# CANbus.net
KiCad netlist of a schematic drawn in Altium Designer
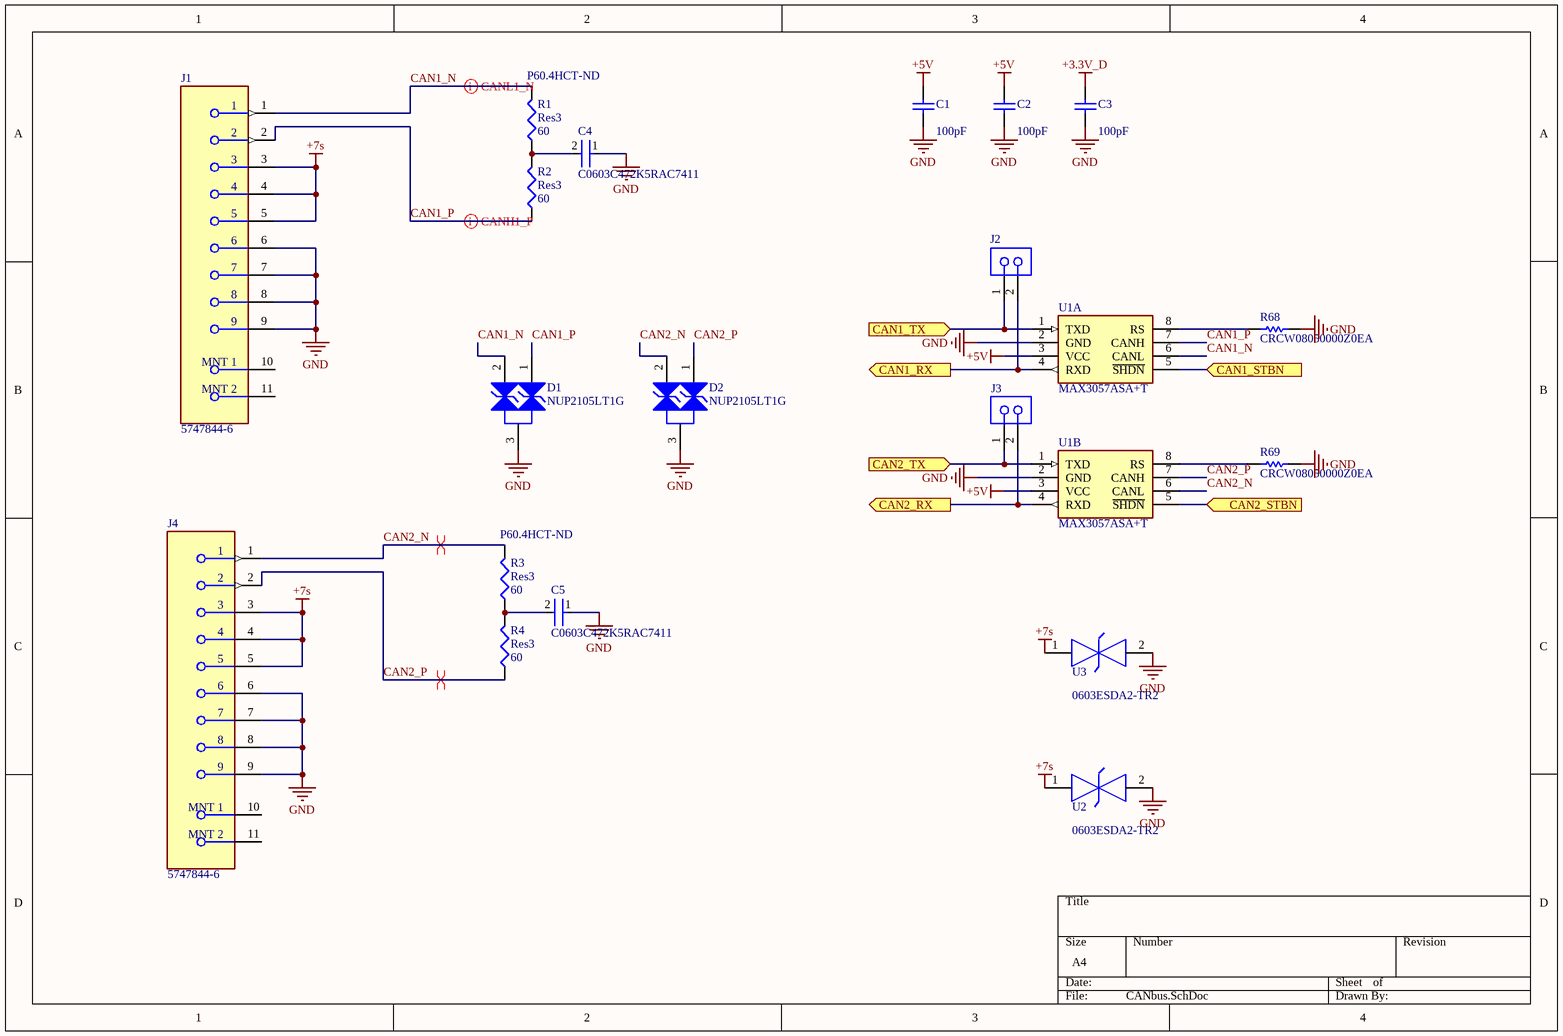
[diagram p0: CANbus.SchDoc]

(export (version "E")
  (design (tool "Eeschema 10.0.6"))
  (components
    (comp (ref "C1")
      (value "100pF")
      (footprint "CAPC1608X90X35NL10T15")
      (fields (field (name "PART NUMBER") "GRM1885C1H101JA01D") (field (name "MANUFACTURER") "Murata"))
      (libsource (lib "Altium Content Vault") (part "CAP"))
    )
    (comp (ref "C2")
      (value "100pF")
      (footprint "CAPC1608X90X35NL10T15")
      (fields (field (name "PART NUMBER") "GRM1885C1H101JA01D") (field (name "MANUFACTURER") "Murata"))
      (libsource (lib "Altium Content Vault") (part "CAP"))
    )
    (comp (ref "C3")
      (value "100pF")
      (footprint "CAPC1608X90X35NL10T15")
      (fields (field (name "PART NUMBER") "GRM1885C1H101JA01D") (field (name "MANUFACTURER") "Murata"))
      (libsource (lib "Altium Content Vault") (part "CAP"))
    )
    (comp (ref "C4")
      (value "C0603C472K5RAC7411")
      (footprint "FP-C0603C-CF-MFG")
      (description "C0603 4,700 pF X7R 30ppm/°C 10.00% 50 V")
      (fields
        (field (name "OCTOPART") "https://octopart.com/c0603c472k5rac7411-kemet-3746251")
        (field (name "TOLERANCE") "0.1")
      )
      (libsource (lib "Altium Content Vault") (part "b4654b650e69147ec39a6b967a45e02"))
    )
    (comp (ref "C5")
      (value "C0603C472K5RAC7411")
      (footprint "FP-C0603C-CF-MFG")
      (description "C0603 4,700 pF X7R 30ppm/°C 10.00% 50 V")
      (fields
        (field (name "OCTOPART") "https://octopart.com/c0603c472k5rac7411-kemet-3746251")
        (field (name "TOLERANCE") "0.1")
      )
      (libsource (lib "Altium Content Vault") (part "b4654b650e69147ec39a6b967a45e02"))
    )
    (comp (ref "D1")
      (value "NUP2105LT1G")
      (footprint "ONSC-SOT-23-3-318-08_V")
      (description "Dual Line CAN Bus Protector, 3-Pin SOT-23, Pb-Free, Tape and Reel")
      (fields (field (name "MANUFACTURER") "On Semiconductor"))
      (libsource (lib "Altium Content Vault") (part "ONSC-NUP21X5X-SOT-23-3-318-08"))
    )
    (comp (ref "D2")
      (value "NUP2105LT1G")
      (footprint "ONSC-SOT-23-3-318-08_V")
      (description "Dual Line CAN Bus Protector, 3-Pin SOT-23, Pb-Free, Tape and Reel")
      (fields (field (name "MANUFACTURER") "On Semiconductor"))
      (libsource (lib "Altium Content Vault") (part "ONSC-NUP21X5X-SOT-23-3-318-08"))
    )
    (comp (ref "J1")
      (value "5747844-6")
      (footprint "FP-5747844-6-MFG")
      (description "CONN D-SUB RCPT 9POS R/A SOLDER")
      (fields
        (field (name "MANUFACTURER") "TE Connectivity")
        (field (name "OCTOPART") "https://octopart.com/5747844-6-te+connectivity-46505427")
      )
      (libsource (lib "Altium Content Vault") (part "18082bb167a0522e34c03a238bc0119"))
    )
    (comp (ref "J2")
      (value "SSW-102-02-T-S")
      (footprint "SMTC-SSW-102-02-X-S")
      (description "SQ Post Socket, Through-hole, Vertical, -55 to 105 degC, 2.54 mm Pitch, 2-Pin, Female, RoHS")
      (fields (field (name "MANUFACTURER") "Samtec"))
      (libsource (lib "Altium Content Vault") (part "SMTC-SSW-102-02-X-S-X"))
    )
    (comp (ref "J3")
      (value "SSW-102-02-T-S")
      (footprint "SMTC-SSW-102-02-X-S")
      (description "SQ Post Socket, Through-hole, Vertical, -55 to 105 degC, 2.54 mm Pitch, 2-Pin, Female, RoHS")
      (fields (field (name "MANUFACTURER") "Samtec"))
      (libsource (lib "Altium Content Vault") (part "SMTC-SSW-102-02-X-S-X"))
    )
    (comp (ref "J4")
      (value "5747844-6")
      (footprint "FP-5747844-6-MFG")
      (description "CONN D-SUB RCPT 9POS R/A SOLDER")
      (fields
        (field (name "MANUFACTURER") "TE Connectivity")
        (field (name "OCTOPART") "https://octopart.com/5747844-6-te+connectivity-46505427")
      )
      (libsource (lib "Altium Content Vault") (part "18082bb167a0522e34c03a238bc0119"))
    )
    (comp (ref "R1")
      (value "Res3")
      (footprint "J1-0603")
      (description "RESISTOR, 0603, 60R4 1%, 0.1W")
      (fields
        (field (name "ALTIUM_VALUE") "60")
        (field (name "SUPPLIER PART NUMBER 1") "P60.4HCT-ND")
        (field (name "MANUFACTURER") "Panasonic")
        (field (name "MANUFACTURER PART NUMBER") "ERJ-3EKF60R4V")
        (field (name "PUBLISHER") "Altium Limited")
      )
      (libsource (lib "Miscellaneous Devices") (part "Res3"))
    )
    (comp (ref "R2")
      (value "Res3")
      (footprint "J1-0603")
      (description "RESISTOR, 0603, 60R4 1%, 0.1W")
      (fields
        (field (name "ALTIUM_VALUE") "60")
        (field (name "MANUFACTURER") "Panasonic")
        (field (name "MANUFACTURER PART NUMBER") "ERJ-3EKF60R4V")
        (field (name "PUBLISHER") "Altium Limited")
      )
      (libsource (lib "Miscellaneous Devices") (part "Res3"))
    )
    (comp (ref "R3")
      (value "Res3")
      (footprint "J1-0603")
      (description "RESISTOR, 0603, 60R4 1%, 0.1W")
      (fields
        (field (name "ALTIUM_VALUE") "60")
        (field (name "SUPPLIER PART NUMBER 1") "P60.4HCT-ND")
        (field (name "MANUFACTURER") "Panasonic")
        (field (name "MANUFACTURER PART NUMBER") "ERJ-3EKF60R4V")
        (field (name "PUBLISHER") "Altium Limited")
      )
      (libsource (lib "Miscellaneous Devices") (part "Res3"))
    )
    (comp (ref "R4")
      (value "Res3")
      (footprint "J1-0603")
      (description "RESISTOR, 0603, 60R4 1%, 0.1W")
      (fields
        (field (name "ALTIUM_VALUE") "60")
        (field (name "MANUFACTURER") "Panasonic")
        (field (name "MANUFACTURER PART NUMBER") "ERJ-3EKF60R4V")
        (field (name "PUBLISHER") "Altium Limited")
      )
      (libsource (lib "Miscellaneous Devices") (part "Res3"))
    )
    (comp (ref "R68")
      (value "CRCW08050000Z0EA")
      (footprint "RESC2013X50X30LL20T20")
      (fields (field (name "MANUFACTURER") "Vishay Dale"))
      (libsource (lib "Altium Content Vault") (part "RES"))
    )
    (comp (ref "R69")
      (value "CRCW08050000Z0EA")
      (footprint "RESC2013X50X30LL20T20")
      (fields (field (name "MANUFACTURER") "Vishay Dale"))
      (libsource (lib "Altium Content Vault") (part "RES"))
    )
    (comp (ref "U1A")
      (value "MAX3057ASA+T")
      (footprint "SamacSys:SOIC127P600X175-8N")
      (description "Integrated Circuit")
      (libsource (lib "*") (part "MAX3057ASA+T"))
    )
    (comp (ref "U1B")
      (value "MAX3057ASA+T")
      (footprint "SamacSys:SOIC127P600X175-8N")
      (description "Integrated Circuit")
      (libsource (lib "*") (part "MAX3057ASA+T"))
    )
    (comp (ref "U2")
      (value "0603ESDA2-TR2")
      (footprint "Eaton_0603ESDA_0")
      (description "DIODE SUPPRESSOR ESD 30VDC 0603 SMD")
      (fields (field (name "DIGIKEY PART NUMBER") "283-4156-1-ND") (field (name "MANUFACTURER") "Eaton"))
      (libsource (lib "EEConcierge") (part "0603ESDA2-TR2"))
    )
    (comp (ref "U3")
      (value "0603ESDA2-TR2")
      (footprint "Eaton_0603ESDA_0")
      (description "DIODE SUPPRESSOR ESD 30VDC 0603 SMD")
      (fields (field (name "DIGIKEY PART NUMBER") "283-4156-1-ND") (field (name "MANUFACTURER") "Eaton"))
      (libsource (lib "EEConcierge") (part "0603ESDA2-TR2"))
    )
  )
  (nets
    (net (code "1") (name "+3.3V_D") (class "Default")
      (node (ref "C3") (pin "2") (pinfunction "2_2") (pintype "passive"))
    )
    (net (code "2") (name "+5V") (class "Default")
      (node (ref "C1") (pin "2") (pinfunction "2_2") (pintype "passive"))
      (node (ref "C2") (pin "2") (pinfunction "2_2") (pintype "passive"))
      (node (ref "U1A") (pin "3") (pinfunction "VCC_3") (pintype "passive"))
      (node (ref "U1B") (pin "3") (pinfunction "VCC_3") (pintype "passive"))
    )
    (net (code "3") (name "+7s") (class "Default")
      (node (ref "J1") (pin "3") (pinfunction "3_3") (pintype "passive"))
      (node (ref "J1") (pin "4") (pinfunction "4_4") (pintype "passive"))
      (node (ref "J1") (pin "5") (pinfunction "5_5") (pintype "passive"))
      (node (ref "J4") (pin "3") (pinfunction "3_3") (pintype "passive"))
      (node (ref "J4") (pin "4") (pinfunction "4_4") (pintype "passive"))
      (node (ref "J4") (pin "5") (pinfunction "5_5") (pintype "passive"))
      (node (ref "U2") (pin "1") (pinfunction "1_1") (pintype "passive"))
      (node (ref "U3") (pin "1") (pinfunction "1_1") (pintype "passive"))
    )
    (net (code "4") (name "/CAN1_N") (class "Default")
      (node (ref "D1") (pin "2") (pinfunction "K_2") (pintype "passive"))
      (node (ref "J1") (pin "1") (pinfunction "1_1") (pintype "output"))
      (node (ref "R1") (pin "2") (pinfunction "2_2") (pintype "passive"))
      (node (ref "U1A") (pin "6") (pinfunction "CANL_6") (pintype "passive"))
    )
    (net (code "5") (name "/CAN1_P") (class "Default")
      (node (ref "D1") (pin "1") (pinfunction "K_1") (pintype "passive"))
      (node (ref "J1") (pin "2") (pinfunction "2_2") (pintype "output"))
      (node (ref "R2") (pin "1") (pinfunction "1_1") (pintype "passive"))
      (node (ref "U1A") (pin "7") (pinfunction "CANH_7") (pintype "passive"))
    )
    (net (code "6") (name "/CAN1_RX") (class "Default")
      (node (ref "J2") (pin "2") (pinfunction "2_2") (pintype "passive"))
      (node (ref "U1A") (pin "4") (pinfunction "RXD_4") (pintype "output"))
    )
    (net (code "7") (name "/CAN1_STBN") (class "Default")
      (node (ref "U1A") (pin "5") (pinfunction "~{SHDN}_5") (pintype "passive"))
    )
    (net (code "8") (name "/CAN1_TX") (class "Default")
      (node (ref "J2") (pin "1") (pinfunction "1_1") (pintype "passive"))
      (node (ref "U1A") (pin "1") (pinfunction "TXD_1") (pintype "input"))
    )
    (net (code "9") (name "/CAN2_N") (class "Default")
      (node (ref "D2") (pin "2") (pinfunction "K_2") (pintype "passive"))
      (node (ref "J4") (pin "1") (pinfunction "1_1") (pintype "output"))
      (node (ref "R3") (pin "2") (pinfunction "2_2") (pintype "passive"))
      (node (ref "U1B") (pin "6") (pinfunction "CANL_6") (pintype "passive"))
    )
    (net (code "10") (name "/CAN2_P") (class "Default")
      (node (ref "D2") (pin "1") (pinfunction "K_1") (pintype "passive"))
      (node (ref "J4") (pin "2") (pinfunction "2_2") (pintype "output"))
      (node (ref "R4") (pin "1") (pinfunction "1_1") (pintype "passive"))
      (node (ref "U1B") (pin "7") (pinfunction "CANH_7") (pintype "passive"))
    )
    (net (code "11") (name "/CAN2_RX") (class "Default")
      (node (ref "J3") (pin "2") (pinfunction "2_2") (pintype "passive"))
      (node (ref "U1B") (pin "4") (pinfunction "RXD_4") (pintype "output"))
    )
    (net (code "12") (name "/CAN2_STBN") (class "Default")
      (node (ref "U1B") (pin "5") (pinfunction "~{SHDN}_5") (pintype "passive"))
    )
    (net (code "13") (name "/CAN2_TX") (class "Default")
      (node (ref "J3") (pin "1") (pinfunction "1_1") (pintype "passive"))
      (node (ref "U1B") (pin "1") (pinfunction "TXD_1") (pintype "input"))
    )
    (net (code "14") (name "GND") (class "Default")
      (node (ref "C1") (pin "1") (pinfunction "1_1") (pintype "passive"))
      (node (ref "C2") (pin "1") (pinfunction "1_1") (pintype "passive"))
      (node (ref "C3") (pin "1") (pinfunction "1_1") (pintype "passive"))
      (node (ref "C4") (pin "1") (pinfunction "1_1") (pintype "passive"))
      (node (ref "C5") (pin "1") (pinfunction "1_1") (pintype "passive"))
      (node (ref "D1") (pin "3") (pinfunction "K_3") (pintype "passive"))
      (node (ref "D2") (pin "3") (pinfunction "K_3") (pintype "passive"))
      (node (ref "J1") (pin "6") (pinfunction "6_6") (pintype "passive"))
      (node (ref "J1") (pin "7") (pinfunction "7_7") (pintype "passive"))
      (node (ref "J1") (pin "8") (pinfunction "8_8") (pintype "passive"))
      (node (ref "J1") (pin "9") (pinfunction "9_9") (pintype "passive"))
      (node (ref "J4") (pin "6") (pinfunction "6_6") (pintype "passive"))
      (node (ref "J4") (pin "7") (pinfunction "7_7") (pintype "passive"))
      (node (ref "J4") (pin "8") (pinfunction "8_8") (pintype "passive"))
      (node (ref "J4") (pin "9") (pinfunction "9_9") (pintype "passive"))
      (node (ref "R68") (pin "2") (pinfunction "2_2") (pintype "passive"))
      (node (ref "R69") (pin "2") (pinfunction "2_2") (pintype "passive"))
      (node (ref "U1A") (pin "2") (pinfunction "GND_2") (pintype "passive"))
      (node (ref "U1B") (pin "2") (pinfunction "GND_2") (pintype "passive"))
      (node (ref "U2") (pin "2") (pinfunction "2_2") (pintype "passive"))
      (node (ref "U3") (pin "2") (pinfunction "2_2") (pintype "passive"))
    )
    (net (code "15") (name "Net-(C4-Pad2)") (class "Default")
      (node (ref "C4") (pin "2") (pinfunction "2_2") (pintype "passive"))
      (node (ref "R1") (pin "1") (pinfunction "1_1") (pintype "passive"))
      (node (ref "R2") (pin "2") (pinfunction "2_2") (pintype "passive"))
    )
    (net (code "16") (name "Net-(C5-Pad2)") (class "Default")
      (node (ref "C5") (pin "2") (pinfunction "2_2") (pintype "passive"))
      (node (ref "R3") (pin "1") (pinfunction "1_1") (pintype "passive"))
      (node (ref "R4") (pin "2") (pinfunction "2_2") (pintype "passive"))
    )
    (net (code "17") (name "Net-(U1A-RS)") (class "Default")
      (node (ref "R68") (pin "1") (pinfunction "1_1") (pintype "passive"))
      (node (ref "U1A") (pin "8") (pinfunction "RS_8") (pintype "passive"))
    )
    (net (code "18") (name "Net-(U1B-RS)") (class "Default")
      (node (ref "R69") (pin "1") (pinfunction "1_1") (pintype "passive"))
      (node (ref "U1B") (pin "8") (pinfunction "RS_8") (pintype "passive"))
    )
    (net (code "19") (name "unconnected-(J1-MNT_1-Pad10)") (class "Default")
      (node (ref "J1") (pin "10") (pinfunction "MNT_1_10") (pintype "passive"))
    )
    (net (code "20") (name "unconnected-(J1-MNT_2-Pad11)") (class "Default")
      (node (ref "J1") (pin "11") (pinfunction "MNT_2_11") (pintype "passive"))
    )
    (net (code "21") (name "unconnected-(J4-MNT_1-Pad10)") (class "Default")
      (node (ref "J4") (pin "10") (pinfunction "MNT_1_10") (pintype "passive"))
    )
    (net (code "22") (name "unconnected-(J4-MNT_2-Pad11)") (class "Default")
      (node (ref "J4") (pin "11") (pinfunction "MNT_2_11") (pintype "passive"))
    )
  )
)
